# PinguinoBase.net
KiCad netlist of a schematic drawn in EAGLE
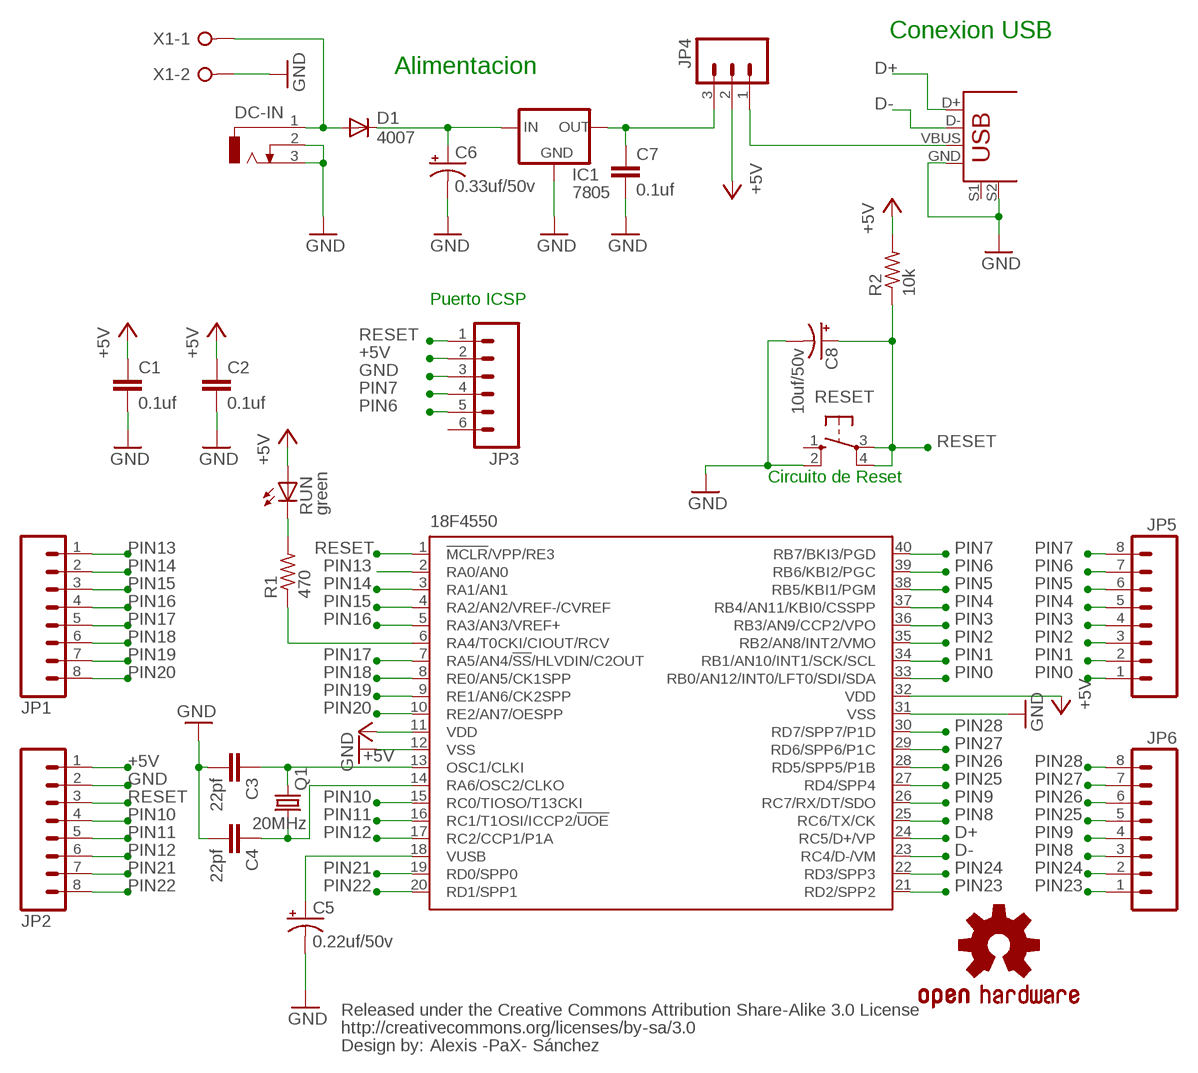
[diagram p0: schematic, sheet 1]

(export (version "E")
  (design (tool "Eeschema 10.0.6"))
  (components
    (comp (ref "18F4550")
      (value "PIC18F4550_40")
      (footprint "eagle-import:DIL40")
      (fields (field (name "MF") "MICROCHIP") (field (name "MPN") "PIC18F4550-I/P"))
      (libsource (lib "eagle-import") (part "PIC18F4_40550"))
    )
    (comp (ref "C1")
      (value "0.1uf")
      (footprint "eagle-import:CAP-PTH-SMALL2")
      (libsource (lib "eagle-import") (part "CAPPTH2"))
    )
    (comp (ref "C2")
      (value "0.1uf")
      (footprint "eagle-import:CAP-PTH-SMALL2")
      (libsource (lib "eagle-import") (part "CAPPTH2"))
    )
    (comp (ref "C3")
      (value "22pf")
      (footprint "eagle-import:CAP-PTH-SMALL2")
      (libsource (lib "eagle-import") (part "CAPPTH2"))
    )
    (comp (ref "C4")
      (value "22pf")
      (footprint "eagle-import:CAP-PTH-SMALL2")
      (libsource (lib "eagle-import") (part "CAPPTH2"))
    )
    (comp (ref "C5")
      (value "0.22uf/50v")
      (footprint "eagle-import:CPOL-RADIAL-10UF-25V")
      (libsource (lib "eagle-import") (part "CAP_POLPTH2"))
    )
    (comp (ref "C6")
      (value "0.33uf/50v")
      (footprint "eagle-import:CPOL-RADIAL-10UF-25V")
      (libsource (lib "eagle-import") (part "CAP_POLPTH2"))
    )
    (comp (ref "C7")
      (value "0.1uf")
      (footprint "eagle-import:CAP-PTH-SMALL2")
      (libsource (lib "eagle-import") (part "CAPPTH2"))
    )
    (comp (ref "C8")
      (value "10uf/50v")
      (footprint "eagle-import:CPOL-RADIAL-10UF-25V")
      (libsource (lib "eagle-import") (part "CAP_POLPTH2"))
    )
    (comp (ref "CC_TEXT1")
      (value "CREATIVE_COMMONS")
      (footprint "eagle-import:CREATIVE_COMMONS")
      (libsource (lib "eagle-import") (part "CREATIVE_COMMONS"))
    )
    (comp (ref "D1")
      (value "4007")
      (footprint "eagle-import:DO35-7")
      (libsource (lib "eagle-import") (part "1N4148DO35-7"))
    )
    (comp (ref "DC-IN")
      (value "DCJ0303")
      (footprint "eagle-import:DCJ0303")
      (libsource (lib "eagle-import") (part "DCJ0303"))
    )
    (comp (ref "IC1")
      (value "7805")
      (footprint "eagle-import:78XXL")
      (libsource (lib "eagle-import") (part "78XXL"))
    )
    (comp (ref "JP1")
      (value "M08LONGPADS")
      (footprint "eagle-import:1X08_LONGPADS")
      (libsource (lib "eagle-import") (part "M08LONGPADS"))
    )
    (comp (ref "JP2")
      (value "M08LONGPADS")
      (footprint "eagle-import:1X08_LONGPADS")
      (libsource (lib "eagle-import") (part "M08LONGPADS"))
    )
    (comp (ref "JP3")
      (value "M06LONGPADS")
      (footprint "eagle-import:1X06_LONGPADS")
      (libsource (lib "eagle-import") (part "M06LONGPADS"))
    )
    (comp (ref "JP4")
      (value "M03LONGPADS")
      (footprint "eagle-import:1X03_LONGPADS")
      (libsource (lib "eagle-import") (part "M03LONGPADS"))
    )
    (comp (ref "JP5")
      (value "M08LONGPADS")
      (footprint "eagle-import:1X08_LONGPADS")
      (libsource (lib "eagle-import") (part "M08LONGPADS"))
    )
    (comp (ref "JP6")
      (value "M08LONGPADS")
      (footprint "eagle-import:1X08_LONGPADS")
      (libsource (lib "eagle-import") (part "M08LONGPADS"))
    )
    (comp (ref "LOGO2")
      (value "OSHW-LOGOL")
      (footprint "eagle-import:OSHW-LOGO-L")
      (libsource (lib "eagle-import") (part "OSHW-LOGOL"))
    )
    (comp (ref "Q1")
      (value "20MHz")
      (footprint "eagle-import:HC49U-V")
      (libsource (lib "eagle-import") (part "CRYSTALHC49U-V"))
    )
    (comp (ref "R1")
      (value "470")
      (footprint "eagle-import:0207_7")
      (libsource (lib "eagle-import") (part "R-US_0207/7"))
    )
    (comp (ref "R2")
      (value "10k")
      (footprint "eagle-import:0207_7")
      (libsource (lib "eagle-import") (part "R-US_0207/7"))
    )
    (comp (ref "RESET")
      (value "10-XX")
      (footprint "eagle-import:B3F-10XX")
      (fields (field (name "MPN") "B3F-1000"))
      (libsource (lib "eagle-import") (part "10-XX"))
    )
    (comp (ref "RUN")
      (value "green")
      (footprint "eagle-import:LED3MM")
      (libsource (lib "eagle-import") (part "LED3MM"))
    )
    (comp (ref "USB")
      (value "USB+SHIELD")
      (footprint "eagle-import:USB-B-PTH")
      (libsource (lib "eagle-import") (part "USB+SHIELD"))
    )
    (comp (ref "X1")
      (value "W237-02P")
      (footprint "eagle-import:W237-132")
      (libsource (lib "eagle-import") (part "W237-02P"))
    )
  )
  (nets
    (net (code "1") (name "+5V") (class "Default")
      (node (ref "18F4550") (pin "11") (pinfunction "VDD_11") (pintype "power_in"))
      (node (ref "18F4550") (pin "32") (pinfunction "VDD_32") (pintype "power_in"))
      (node (ref "C1") (pin "1") (pinfunction "1_1") (pintype "passive"))
      (node (ref "C2") (pin "1") (pinfunction "1_1") (pintype "passive"))
      (node (ref "JP2") (pin "1") (pinfunction "1_1") (pintype "passive"))
      (node (ref "JP3") (pin "2") (pinfunction "2_2") (pintype "passive"))
      (node (ref "JP4") (pin "2") (pinfunction "2_2") (pintype "passive"))
      (node (ref "R2") (pin "2") (pinfunction "2_2") (pintype "passive"))
      (node (ref "RUN") (pin "A") (pinfunction "A_A") (pintype "passive"))
    )
    (net (code "2") (name "/D+") (class "Default")
      (node (ref "18F4550") (pin "24") (pinfunction "RC5/D+/VP_24") (pintype "bidirectional"))
      (node (ref "USB") (pin "D+") (pinfunction "D+_D+") (pintype "bidirectional"))
    )
    (net (code "3") (name "/D-") (class "Default")
      (node (ref "18F4550") (pin "23") (pinfunction "RC4/D-/VM_23") (pintype "bidirectional"))
      (node (ref "USB") (pin "D-") (pinfunction "D-_D-") (pintype "bidirectional"))
    )
    (net (code "4") (name "/PIN0") (class "Default")
      (node (ref "18F4550") (pin "33") (pinfunction "RB0/AN12/INT0/LFT0/SDI/SDA_33") (pintype "bidirectional"))
      (node (ref "JP5") (pin "1") (pinfunction "1_1") (pintype "passive"))
    )
    (net (code "5") (name "/PIN1") (class "Default")
      (node (ref "18F4550") (pin "34") (pinfunction "RB1/AN10/INT1/SCK/SCL_34") (pintype "bidirectional"))
      (node (ref "JP5") (pin "2") (pinfunction "2_2") (pintype "passive"))
    )
    (net (code "6") (name "/PIN2") (class "Default")
      (node (ref "18F4550") (pin "35") (pinfunction "RB2/AN8/INT2/VMO_35") (pintype "bidirectional"))
      (node (ref "JP5") (pin "3") (pinfunction "3_3") (pintype "passive"))
    )
    (net (code "7") (name "/PIN3") (class "Default")
      (node (ref "18F4550") (pin "36") (pinfunction "RB3/AN9/CCP2/VPO_36") (pintype "bidirectional"))
      (node (ref "JP5") (pin "4") (pinfunction "4_4") (pintype "passive"))
    )
    (net (code "8") (name "/PIN4") (class "Default")
      (node (ref "18F4550") (pin "37") (pinfunction "RB4/AN11/KBI0/CSSPP_37") (pintype "bidirectional"))
      (node (ref "JP5") (pin "5") (pinfunction "5_5") (pintype "passive"))
    )
    (net (code "9") (name "/PIN5") (class "Default")
      (node (ref "18F4550") (pin "38") (pinfunction "RB5/KBI1/PGM_38") (pintype "bidirectional"))
      (node (ref "JP5") (pin "6") (pinfunction "6_6") (pintype "passive"))
    )
    (net (code "10") (name "/PIN6") (class "Default")
      (node (ref "18F4550") (pin "39") (pinfunction "RB6/KBI2/PGC_39") (pintype "bidirectional"))
      (node (ref "JP3") (pin "5") (pinfunction "5_5") (pintype "passive"))
      (node (ref "JP5") (pin "7") (pinfunction "7_7") (pintype "passive"))
    )
    (net (code "11") (name "/PIN7") (class "Default")
      (node (ref "18F4550") (pin "40") (pinfunction "RB7/BKI3/PGD_40") (pintype "bidirectional"))
      (node (ref "JP3") (pin "4") (pinfunction "4_4") (pintype "passive"))
      (node (ref "JP5") (pin "8") (pinfunction "8_8") (pintype "passive"))
    )
    (net (code "12") (name "/PIN8") (class "Default")
      (node (ref "18F4550") (pin "25") (pinfunction "RC6/TX/CK_25") (pintype "bidirectional"))
      (node (ref "JP6") (pin "3") (pinfunction "3_3") (pintype "passive"))
    )
    (net (code "13") (name "/PIN9") (class "Default")
      (node (ref "18F4550") (pin "26") (pinfunction "RC7/RX/DT/SDO_26") (pintype "bidirectional"))
      (node (ref "JP6") (pin "4") (pinfunction "4_4") (pintype "passive"))
    )
    (net (code "14") (name "/PIN10") (class "Default")
      (node (ref "18F4550") (pin "15") (pinfunction "RC0/TIOSO/T13CKI_15") (pintype "bidirectional"))
      (node (ref "JP2") (pin "4") (pinfunction "4_4") (pintype "passive"))
    )
    (net (code "15") (name "/PIN11") (class "Default")
      (node (ref "18F4550") (pin "16") (pinfunction "RC1/T1OSI/ICCP2/~{UOE}_16") (pintype "bidirectional"))
      (node (ref "JP2") (pin "5") (pinfunction "5_5") (pintype "passive"))
    )
    (net (code "16") (name "/PIN12") (class "Default")
      (node (ref "18F4550") (pin "17") (pinfunction "RC2/CCP1/P1A_17") (pintype "bidirectional"))
      (node (ref "JP2") (pin "6") (pinfunction "6_6") (pintype "passive"))
    )
    (net (code "17") (name "/PIN13") (class "Default")
      (node (ref "18F4550") (pin "2") (pinfunction "RA0/AN0_2") (pintype "bidirectional"))
      (node (ref "JP1") (pin "1") (pinfunction "1_1") (pintype "passive"))
    )
    (net (code "18") (name "/PIN14") (class "Default")
      (node (ref "18F4550") (pin "3") (pinfunction "RA1/AN1_3") (pintype "bidirectional"))
      (node (ref "JP1") (pin "2") (pinfunction "2_2") (pintype "passive"))
    )
    (net (code "19") (name "/PIN15") (class "Default")
      (node (ref "18F4550") (pin "4") (pinfunction "RA2/AN2/VREF-/CVREF_4") (pintype "bidirectional"))
      (node (ref "JP1") (pin "3") (pinfunction "3_3") (pintype "passive"))
    )
    (net (code "20") (name "/PIN16") (class "Default")
      (node (ref "18F4550") (pin "5") (pinfunction "RA3/AN3/VREF+_5") (pintype "bidirectional"))
      (node (ref "JP1") (pin "4") (pinfunction "4_4") (pintype "passive"))
    )
    (net (code "21") (name "/PIN17") (class "Default")
      (node (ref "18F4550") (pin "7") (pinfunction "RA5/AN4/~{SS}/HLVDIN/C2OUT_7") (pintype "bidirectional"))
      (node (ref "JP1") (pin "5") (pinfunction "5_5") (pintype "passive"))
    )
    (net (code "22") (name "/PIN18") (class "Default")
      (node (ref "18F4550") (pin "8") (pinfunction "RE0/AN5/CK1SPP_8") (pintype "bidirectional"))
      (node (ref "JP1") (pin "6") (pinfunction "6_6") (pintype "passive"))
    )
    (net (code "23") (name "/PIN19") (class "Default")
      (node (ref "18F4550") (pin "9") (pinfunction "RE1/AN6/CK2SPP_9") (pintype "bidirectional"))
      (node (ref "JP1") (pin "7") (pinfunction "7_7") (pintype "passive"))
    )
    (net (code "24") (name "/PIN20") (class "Default")
      (node (ref "18F4550") (pin "10") (pinfunction "RE2/AN7/OESPP_10") (pintype "bidirectional"))
      (node (ref "JP1") (pin "8") (pinfunction "8_8") (pintype "passive"))
    )
    (net (code "25") (name "/PIN21") (class "Default")
      (node (ref "18F4550") (pin "19") (pinfunction "RD0/SPP0_19") (pintype "bidirectional"))
      (node (ref "JP2") (pin "7") (pinfunction "7_7") (pintype "passive"))
    )
    (net (code "26") (name "/PIN22") (class "Default")
      (node (ref "18F4550") (pin "20") (pinfunction "RD1/SPP1_20") (pintype "bidirectional"))
      (node (ref "JP2") (pin "8") (pinfunction "8_8") (pintype "passive"))
    )
    (net (code "27") (name "/PIN23") (class "Default")
      (node (ref "18F4550") (pin "21") (pinfunction "RD2/SPP2_21") (pintype "bidirectional"))
      (node (ref "JP6") (pin "1") (pinfunction "1_1") (pintype "passive"))
    )
    (net (code "28") (name "/PIN24") (class "Default")
      (node (ref "18F4550") (pin "22") (pinfunction "RD3/SPP3_22") (pintype "bidirectional"))
      (node (ref "JP6") (pin "2") (pinfunction "2_2") (pintype "passive"))
    )
    (net (code "29") (name "/PIN25") (class "Default")
      (node (ref "18F4550") (pin "27") (pinfunction "RD4/SPP4_27") (pintype "bidirectional"))
      (node (ref "JP6") (pin "5") (pinfunction "5_5") (pintype "passive"))
    )
    (net (code "30") (name "/PIN26") (class "Default")
      (node (ref "18F4550") (pin "28") (pinfunction "RD5/SPP5/P1B_28") (pintype "bidirectional"))
      (node (ref "JP6") (pin "6") (pinfunction "6_6") (pintype "passive"))
    )
    (net (code "31") (name "/PIN27") (class "Default")
      (node (ref "18F4550") (pin "29") (pinfunction "RD6/SPP6/P1C_29") (pintype "bidirectional"))
      (node (ref "JP6") (pin "7") (pinfunction "7_7") (pintype "passive"))
    )
    (net (code "32") (name "/PIN28") (class "Default")
      (node (ref "18F4550") (pin "30") (pinfunction "RD7/SPP7/P1D_30") (pintype "bidirectional"))
      (node (ref "JP6") (pin "8") (pinfunction "8_8") (pintype "passive"))
    )
    (net (code "33") (name "/RESET") (class "Default")
      (node (ref "18F4550") (pin "1") (pinfunction "~{MCLR}/VPP/RE3_1") (pintype "input"))
      (node (ref "C8") (pin "1") (pinfunction "+_1") (pintype "passive"))
      (node (ref "JP2") (pin "3") (pinfunction "3_3") (pintype "passive"))
      (node (ref "JP3") (pin "1") (pinfunction "1_1") (pintype "passive"))
      (node (ref "R2") (pin "1") (pinfunction "1_1") (pintype "passive"))
      (node (ref "RESET") (pin "3") (pinfunction "P_3") (pintype "passive"))
      (node (ref "RESET") (pin "4") (pinfunction "P1_4") (pintype "passive"))
    )
    (net (code "34") (name "GND") (class "Default")
      (node (ref "18F4550") (pin "12") (pinfunction "VSS_12") (pintype "power_in"))
      (node (ref "18F4550") (pin "31") (pinfunction "VSS_31") (pintype "power_in"))
      (node (ref "C1") (pin "2") (pinfunction "2_2") (pintype "passive"))
      (node (ref "C2") (pin "2") (pinfunction "2_2") (pintype "passive"))
      (node (ref "C3") (pin "2") (pinfunction "2_2") (pintype "passive"))
      (node (ref "C4") (pin "2") (pinfunction "2_2") (pintype "passive"))
      (node (ref "C5") (pin "2") (pinfunction "-_2") (pintype "passive"))
      (node (ref "C6") (pin "2") (pinfunction "-_2") (pintype "passive"))
      (node (ref "C7") (pin "2") (pinfunction "2_2") (pintype "passive"))
      (node (ref "C8") (pin "2") (pinfunction "-_2") (pintype "passive"))
      (node (ref "DC-IN") (pin "2") (pinfunction "2_2") (pintype "passive"))
      (node (ref "DC-IN") (pin "3") (pinfunction "3_3") (pintype "passive"))
      (node (ref "IC1") (pin "GND") (pinfunction "GND_GND") (pintype "input"))
      (node (ref "JP2") (pin "2") (pinfunction "2_2") (pintype "passive"))
      (node (ref "JP3") (pin "3") (pinfunction "3_3") (pintype "passive"))
      (node (ref "RESET") (pin "2") (pinfunction "S1_2") (pintype "passive"))
      (node (ref "USB") (pin "GND") (pinfunction "GND_GND") (pintype "bidirectional"))
      (node (ref "USB") (pin "S2") (pinfunction "P$2_S2") (pintype "bidirectional"))
      (node (ref "X1") (pin "2") (pinfunction "KL_2") (pintype "passive"))
    )
    (net (code "35") (name "Net-(18F4550-OSC1{slash}CLKI)") (class "Default")
      (node (ref "18F4550") (pin "13") (pinfunction "OSC1/CLKI_13") (pintype "input"))
      (node (ref "C3") (pin "1") (pinfunction "1_1") (pintype "passive"))
      (node (ref "Q1") (pin "1") (pinfunction "1_1") (pintype "passive"))
    )
    (net (code "36") (name "Net-(18F4550-RA4{slash}T0CKI{slash}CIOUT{slash}RCV)") (class "Default")
      (node (ref "18F4550") (pin "6") (pinfunction "RA4/T0CKI/CIOUT/RCV_6") (pintype "bidirectional"))
      (node (ref "R1") (pin "1") (pinfunction "1_1") (pintype "passive"))
    )
    (net (code "37") (name "Net-(18F4550-RA6{slash}OSC2{slash}CLKO)") (class "Default")
      (node (ref "18F4550") (pin "14") (pinfunction "RA6/OSC2/CLKO_14") (pintype "output"))
      (node (ref "C4") (pin "1") (pinfunction "1_1") (pintype "passive"))
      (node (ref "Q1") (pin "2") (pinfunction "2_2") (pintype "passive"))
    )
    (net (code "38") (name "Net-(18F4550-VUSB)") (class "Default")
      (node (ref "18F4550") (pin "18") (pinfunction "VUSB_18") (pintype "bidirectional"))
      (node (ref "C5") (pin "1") (pinfunction "+_1") (pintype "passive"))
    )
    (net (code "39") (name "Net-(C6-+)") (class "Default")
      (node (ref "C6") (pin "1") (pinfunction "+_1") (pintype "passive"))
      (node (ref "D1") (pin "C") (pinfunction "C_C") (pintype "passive"))
      (node (ref "IC1") (pin "IN") (pinfunction "IN_IN") (pintype "input"))
    )
    (net (code "40") (name "Net-(C7-Pad1)") (class "Default")
      (node (ref "C7") (pin "1") (pinfunction "1_1") (pintype "passive"))
      (node (ref "IC1") (pin "OUT") (pinfunction "OUT_OUT") (pintype "passive"))
      (node (ref "JP4") (pin "3") (pinfunction "3_3") (pintype "passive"))
    )
    (net (code "41") (name "Net-(JP4-Pad1)") (class "Default")
      (node (ref "JP4") (pin "1") (pinfunction "1_1") (pintype "passive"))
      (node (ref "USB") (pin "VBUS") (pinfunction "VBUS_VBUS") (pintype "bidirectional"))
    )
    (net (code "42") (name "Net-(RUN-C)") (class "Default")
      (node (ref "R1") (pin "2") (pinfunction "2_2") (pintype "passive"))
      (node (ref "RUN") (pin "K") (pinfunction "C_K") (pintype "passive"))
    )
    (net (code "43") (name "Net-(X1A-KL)") (class "Default")
      (node (ref "D1") (pin "A") (pinfunction "A_A") (pintype "passive"))
      (node (ref "DC-IN") (pin "1") (pinfunction "1_1") (pintype "passive"))
      (node (ref "X1") (pin "1") (pinfunction "KL_1") (pintype "passive"))
    )
    (net (code "44") (name "unconnected-(JP3-Pad6)") (class "Default")
      (node (ref "JP3") (pin "6") (pinfunction "6_6") (pintype "passive"))
    )
    (net (code "45") (name "unconnected-(RESET-S-Pad1)") (class "Default")
      (node (ref "RESET") (pin "1") (pinfunction "S_1") (pintype "passive"))
    )
    (net (code "46") (name "unconnected-(USB-P$1-PadS1)") (class "Default")
      (node (ref "USB") (pin "S1") (pinfunction "P$1_S1") (pintype "bidirectional"))
    )
  )
)
